# ServoEncoder.net
KiCad netlist of a schematic drawn in EAGLE
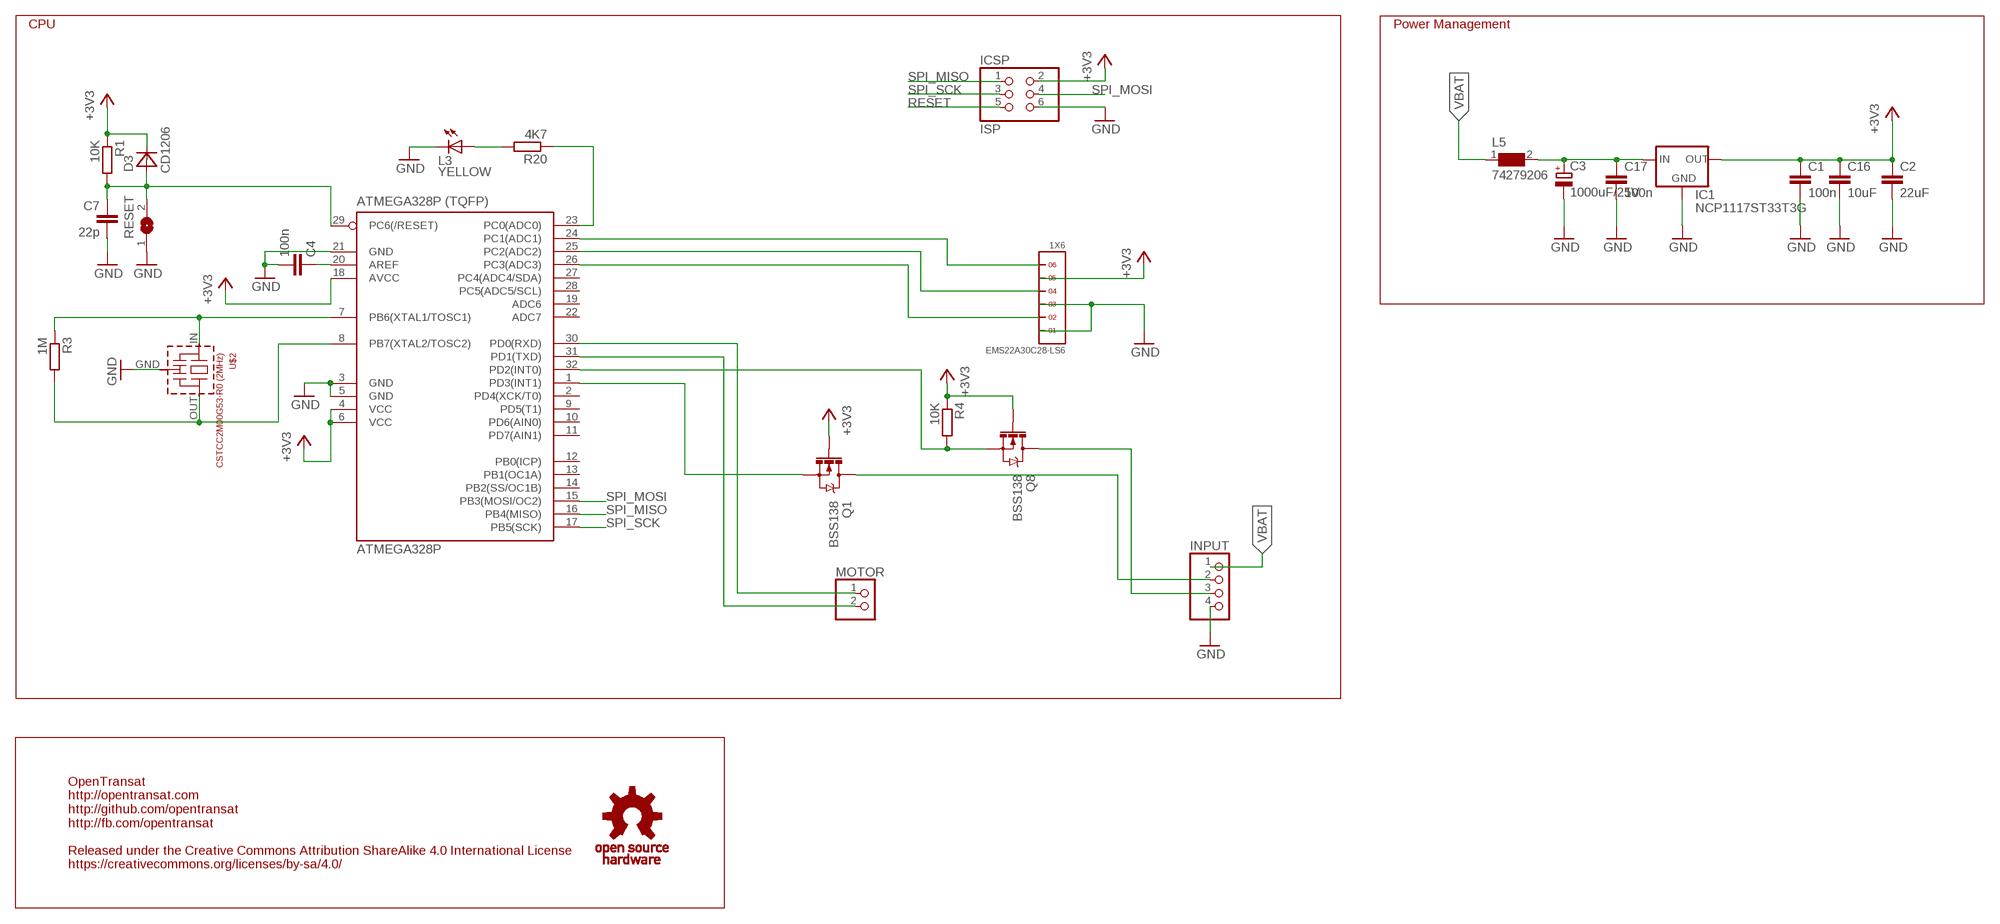
[diagram p0: schematic, sheet 1]

(export (version "E")
  (design (tool "Eeschema 10.0.6"))
  (components
    (comp (ref "ATMEGA328P")
      (value "ATMEGA328P (TQFP)")
      (footprint "eagle-import:TQFP32-08")
      (fields (field (name "MPN") "ATMEGA8-16AU"))
      (libsource (lib "eagle-import") (part "MEGA8-AI"))
    )
    (comp (ref "C1")
      (value "100n")
      (footprint "eagle-import:C0603")
      (libsource (lib "eagle-import") (part "C-EUC0603"))
    )
    (comp (ref "C2")
      (value "22uF")
      (footprint "eagle-import:C1210")
      (libsource (lib "eagle-import") (part "C-EUC1210"))
    )
    (comp (ref "C3")
      (value "1000uF/25V")
      (footprint "eagle-import:E5-10,5")
      (libsource (lib "eagle-import") (part "CPOL-EUE5-10.5"))
    )
    (comp (ref "C4")
      (value "100n")
      (footprint "eagle-import:C0603")
      (libsource (lib "eagle-import") (part "C-EUC0603"))
    )
    (comp (ref "C7")
      (value "22p")
      (footprint "eagle-import:C0603")
      (libsource (lib "eagle-import") (part "C-EUC0603"))
    )
    (comp (ref "C16")
      (value "10uF")
      (footprint "eagle-import:C1206")
      (libsource (lib "eagle-import") (part "C-EUC1206"))
    )
    (comp (ref "C17")
      (value "100n")
      (footprint "eagle-import:C0603")
      (libsource (lib "eagle-import") (part "C-EUC0603"))
    )
    (comp (ref "D3")
      (value "CD1206")
      (footprint "eagle-import:R1206")
      (libsource (lib "eagle-import") (part "CD1206"))
    )
    (comp (ref "EMS22A30C28-LS6")
      (value "1X6")
      (footprint "eagle-import:1X6")
      (libsource (lib "eagle-import") (part "1X6"))
    )
    (comp (ref "IC1")
      (value "NCP1117ST33T3G")
      (footprint "eagle-import:SOT223")
      (fields (field (name "MF") "Texas Instruments") (field (name "MPN") "LM1117MP-3.3"))
      (libsource (lib "eagle-import") (part "LM1117?-MP3.3"))
    )
    (comp (ref "ICSP")
      (value "ISP")
      (footprint "eagle-import:2X03")
      (libsource (lib "eagle-import") (part "PINHD-2X3"))
    )
    (comp (ref "INPUT")
      (value "PINHD-1X4")
      (footprint "eagle-import:1X04")
      (libsource (lib "eagle-import") (part "PINHD-1X4"))
    )
    (comp (ref "L3")
      (value "YELLOW")
      (footprint "eagle-import:CHIPLED_0805")
      (libsource (lib "eagle-import") (part "LEDCHIPLED_0805"))
    )
    (comp (ref "L5")
      (value "74279206")
      (footprint "eagle-import:0805")
      (libsource (lib "eagle-import") (part "WE-CBF_0805"))
    )
    (comp (ref "MOTOR")
      (value "PINHD-1X2")
      (footprint "eagle-import:1X02")
      (libsource (lib "eagle-import") (part "PINHD-1X2"))
    )
    (comp (ref "Q1")
      (value "BSS138")
      (footprint "eagle-import:SOT23-3")
      (libsource (lib "eagle-import") (part "MOSFET-NCHANNEL_SOT23-3"))
    )
    (comp (ref "Q8")
      (value "BSS138")
      (footprint "eagle-import:SOT23-3")
      (libsource (lib "eagle-import") (part "MOSFET-NCHANNEL_SOT23-3"))
    )
    (comp (ref "R1")
      (value "10K")
      (footprint "eagle-import:R0603")
      (libsource (lib "eagle-import") (part "R-EU_R0603"))
    )
    (comp (ref "R3")
      (value "1M")
      (footprint "eagle-import:R0603")
      (libsource (lib "eagle-import") (part "R-EU_R0603"))
    )
    (comp (ref "R4")
      (value "10K")
      (footprint "eagle-import:R0603")
      (libsource (lib "eagle-import") (part "R-EU_R0603"))
    )
    (comp (ref "R20")
      (value "4K7")
      (footprint "eagle-import:R0603")
      (libsource (lib "eagle-import") (part "R-EU_R0603"))
    )
    (comp (ref "RESET")
      (value "SJW")
      (footprint "eagle-import:SJW")
      (libsource (lib "eagle-import") (part "SJW"))
    )
    (comp (ref "U$1")
      (value "OSHW_S")
      (footprint "eagle-import:OSHWS")
      (libsource (lib "eagle-import") (part "OSHW_S"))
    )
    (comp (ref "U$2")
      (value "CSTCC2M00G53-R0 (2MHz)")
      (footprint "eagle-import:CSTCC")
      (libsource (lib "eagle-import") (part "CSTCC"))
    )
  )
  (nets
    (net (code "1") (name "+3V3") (class "Default")
      (node (ref "ATMEGA328P") (pin "18") (pinfunction "AVCC_18") (pintype "power_in"))
      (node (ref "ATMEGA328P") (pin "4") (pinfunction "VCC_4") (pintype "power_in"))
      (node (ref "ATMEGA328P") (pin "6") (pinfunction "VCC_6") (pintype "power_in"))
      (node (ref "C1") (pin "1") (pinfunction "1_1") (pintype "passive"))
      (node (ref "C16") (pin "1") (pinfunction "1_1") (pintype "passive"))
      (node (ref "C2") (pin "1") (pinfunction "1_1") (pintype "passive"))
      (node (ref "D3") (pin "2") (pinfunction "C_2") (pintype "passive"))
      (node (ref "EMS22A30C28-LS6") (pin "5") (pinfunction "5_5") (pintype "bidirectional"))
      (node (ref "IC1") (pin "2") (pinfunction "OUT_2") (pintype "passive"))
      (node (ref "IC1") (pin "4") (pinfunction "OUT_4") (pintype "passive"))
      (node (ref "ICSP") (pin "2") (pinfunction "2_2") (pintype "passive"))
      (node (ref "Q1") (pin "1") (pinfunction "G_1") (pintype "passive"))
      (node (ref "Q8") (pin "1") (pinfunction "G_1") (pintype "passive"))
      (node (ref "R1") (pin "1") (pinfunction "1_1") (pintype "passive"))
      (node (ref "R4") (pin "1") (pinfunction "1_1") (pintype "passive"))
    )
    (net (code "2") (name "/RESET") (class "Default")
      (node (ref "ATMEGA328P") (pin "29") (pinfunction "PC6(/RESET)_29") (pintype "bidirectional"))
      (node (ref "C7") (pin "1") (pinfunction "1_1") (pintype "passive"))
      (node (ref "D3") (pin "1") (pinfunction "A_1") (pintype "passive"))
      (node (ref "ICSP") (pin "5") (pinfunction "5_5") (pintype "passive"))
      (node (ref "R1") (pin "2") (pinfunction "2_2") (pintype "passive"))
      (node (ref "RESET") (pin "2") (pinfunction "2_2") (pintype "passive"))
    )
    (net (code "3") (name "/SPI_MISO") (class "Default")
      (node (ref "ATMEGA328P") (pin "16") (pinfunction "PB4(MISO)_16") (pintype "bidirectional"))
      (node (ref "ICSP") (pin "1") (pinfunction "1_1") (pintype "passive"))
    )
    (net (code "4") (name "/SPI_MOSI") (class "Default")
      (node (ref "ATMEGA328P") (pin "15") (pinfunction "PB3(MOSI/OC2)_15") (pintype "bidirectional"))
      (node (ref "ICSP") (pin "4") (pinfunction "4_4") (pintype "passive"))
    )
    (net (code "5") (name "/SPI_SCK") (class "Default")
      (node (ref "ATMEGA328P") (pin "17") (pinfunction "PB5(SCK)_17") (pintype "bidirectional"))
      (node (ref "ICSP") (pin "3") (pinfunction "3_3") (pintype "passive"))
    )
    (net (code "6") (name "GND") (class "Default")
      (node (ref "ATMEGA328P") (pin "21") (pinfunction "GND_21") (pintype "power_in"))
      (node (ref "ATMEGA328P") (pin "3") (pinfunction "GND_3") (pintype "power_in"))
      (node (ref "ATMEGA328P") (pin "5") (pinfunction "GND_5") (pintype "power_in"))
      (node (ref "C1") (pin "2") (pinfunction "2_2") (pintype "passive"))
      (node (ref "C16") (pin "2") (pinfunction "2_2") (pintype "passive"))
      (node (ref "C17") (pin "2") (pinfunction "2_2") (pintype "passive"))
      (node (ref "C2") (pin "2") (pinfunction "2_2") (pintype "passive"))
      (node (ref "C3") (pin "-") (pinfunction "-_-") (pintype "passive"))
      (node (ref "C4") (pin "2") (pinfunction "2_2") (pintype "passive"))
      (node (ref "C7") (pin "2") (pinfunction "2_2") (pintype "passive"))
      (node (ref "EMS22A30C28-LS6") (pin "1") (pinfunction "1_1") (pintype "bidirectional"))
      (node (ref "EMS22A30C28-LS6") (pin "3") (pinfunction "3_3") (pintype "bidirectional"))
      (node (ref "IC1") (pin "1") (pinfunction "GND_1") (pintype "input"))
      (node (ref "ICSP") (pin "6") (pinfunction "6_6") (pintype "passive"))
      (node (ref "INPUT") (pin "4") (pinfunction "4_4") (pintype "passive"))
      (node (ref "L3") (pin "C") (pinfunction "C_C") (pintype "passive"))
      (node (ref "RESET") (pin "1") (pinfunction "1_1") (pintype "passive"))
      (node (ref "U$2") (pin "GND") (pinfunction "GND_GND") (pintype "power_in"))
    )
    (net (code "7") (name "Net-(ATMEGA328P-AREF)") (class "Default")
      (node (ref "ATMEGA328P") (pin "20") (pinfunction "AREF_20") (pintype "passive"))
      (node (ref "C4") (pin "1") (pinfunction "1_1") (pintype "passive"))
    )
    (net (code "8") (name "Net-(ATMEGA328P-PB6(XTAL1{slash}TOSC1))") (class "Default")
      (node (ref "ATMEGA328P") (pin "7") (pinfunction "PB6(XTAL1/TOSC1)_7") (pintype "bidirectional"))
      (node (ref "R3") (pin "1") (pinfunction "1_1") (pintype "passive"))
      (node (ref "U$2") (pin "IN") (pinfunction "IN_IN") (pintype "input"))
    )
    (net (code "9") (name "Net-(ATMEGA328P-PB7(XTAL2{slash}TOSC2))") (class "Default")
      (node (ref "ATMEGA328P") (pin "8") (pinfunction "PB7(XTAL2/TOSC2)_8") (pintype "bidirectional"))
      (node (ref "R3") (pin "2") (pinfunction "2_2") (pintype "passive"))
      (node (ref "U$2") (pin "OUT") (pinfunction "OUT_OUT") (pintype "output"))
    )
    (net (code "10") (name "Net-(ATMEGA328P-PC0(ADC0))") (class "Default")
      (node (ref "ATMEGA328P") (pin "23") (pinfunction "PC0(ADC0)_23") (pintype "bidirectional"))
      (node (ref "R20") (pin "1") (pinfunction "1_1") (pintype "passive"))
    )
    (net (code "11") (name "Net-(ATMEGA328P-PC1(ADC1))") (class "Default")
      (node (ref "ATMEGA328P") (pin "24") (pinfunction "PC1(ADC1)_24") (pintype "bidirectional"))
      (node (ref "EMS22A30C28-LS6") (pin "6") (pinfunction "6_6") (pintype "bidirectional"))
    )
    (net (code "12") (name "Net-(ATMEGA328P-PC2(ADC2))") (class "Default")
      (node (ref "ATMEGA328P") (pin "25") (pinfunction "PC2(ADC2)_25") (pintype "bidirectional"))
      (node (ref "EMS22A30C28-LS6") (pin "4") (pinfunction "4_4") (pintype "bidirectional"))
    )
    (net (code "13") (name "Net-(ATMEGA328P-PC3(ADC3))") (class "Default")
      (node (ref "ATMEGA328P") (pin "26") (pinfunction "PC3(ADC3)_26") (pintype "bidirectional"))
      (node (ref "EMS22A30C28-LS6") (pin "2") (pinfunction "2_2") (pintype "bidirectional"))
    )
    (net (code "14") (name "Net-(ATMEGA328P-PD0(RXD))") (class "Default")
      (node (ref "ATMEGA328P") (pin "30") (pinfunction "PD0(RXD)_30") (pintype "bidirectional"))
      (node (ref "MOTOR") (pin "1") (pinfunction "1_1") (pintype "passive"))
    )
    (net (code "15") (name "Net-(ATMEGA328P-PD1(TXD))") (class "Default")
      (node (ref "ATMEGA328P") (pin "31") (pinfunction "PD1(TXD)_31") (pintype "bidirectional"))
      (node (ref "MOTOR") (pin "2") (pinfunction "2_2") (pintype "passive"))
    )
    (net (code "16") (name "Net-(ATMEGA328P-PD2(INT0))") (class "Default")
      (node (ref "ATMEGA328P") (pin "32") (pinfunction "PD2(INT0)_32") (pintype "bidirectional"))
      (node (ref "Q8") (pin "2") (pinfunction "S_2") (pintype "passive"))
      (node (ref "R4") (pin "2") (pinfunction "2_2") (pintype "passive"))
    )
    (net (code "17") (name "Net-(ATMEGA328P-PD3(INT1))") (class "Default")
      (node (ref "ATMEGA328P") (pin "1") (pinfunction "PD3(INT1)_1") (pintype "bidirectional"))
      (node (ref "Q1") (pin "2") (pinfunction "S_2") (pintype "passive"))
    )
    (net (code "18") (name "Net-(IC1-IN)") (class "Default")
      (node (ref "C17") (pin "1") (pinfunction "1_1") (pintype "passive"))
      (node (ref "C3") (pin "+") (pinfunction "+_+") (pintype "passive"))
      (node (ref "IC1") (pin "3") (pinfunction "IN_3") (pintype "input"))
      (node (ref "L5") (pin "2") (pinfunction "2_2") (pintype "passive"))
    )
    (net (code "19") (name "Net-(L3-PadA)") (class "Default")
      (node (ref "L3") (pin "A") (pinfunction "A_A") (pintype "passive"))
      (node (ref "R20") (pin "2") (pinfunction "2_2") (pintype "passive"))
    )
    (net (code "20") (name "Net-(Q1-D)") (class "Default")
      (node (ref "INPUT") (pin "2") (pinfunction "2_2") (pintype "passive"))
      (node (ref "Q1") (pin "3") (pinfunction "D_3") (pintype "passive"))
    )
    (net (code "21") (name "Net-(Q8-D)") (class "Default")
      (node (ref "INPUT") (pin "3") (pinfunction "3_3") (pintype "passive"))
      (node (ref "Q8") (pin "3") (pinfunction "D_3") (pintype "passive"))
    )
    (net (code "22") (name "VBAT") (class "Default")
      (node (ref "INPUT") (pin "1") (pinfunction "1_1") (pintype "passive"))
      (node (ref "L5") (pin "1") (pinfunction "1_1") (pintype "passive"))
    )
    (net (code "23") (name "unconnected-(ATMEGA328P-ADC6-Pad19)") (class "Default")
      (node (ref "ATMEGA328P") (pin "19") (pinfunction "ADC6_19") (pintype "bidirectional"))
    )
    (net (code "24") (name "unconnected-(ATMEGA328P-ADC7-Pad22)") (class "Default")
      (node (ref "ATMEGA328P") (pin "22") (pinfunction "ADC7_22") (pintype "bidirectional"))
    )
    (net (code "25") (name "unconnected-(ATMEGA328P-PB0(ICP)-Pad12)") (class "Default")
      (node (ref "ATMEGA328P") (pin "12") (pinfunction "PB0(ICP)_12") (pintype "bidirectional"))
    )
    (net (code "26") (name "unconnected-(ATMEGA328P-PB1(OC1A)-Pad13)") (class "Default")
      (node (ref "ATMEGA328P") (pin "13") (pinfunction "PB1(OC1A)_13") (pintype "bidirectional"))
    )
    (net (code "27") (name "unconnected-(ATMEGA328P-PB2(SS{slash}OC1B)-Pad14)") (class "Default")
      (node (ref "ATMEGA328P") (pin "14") (pinfunction "PB2(SS/OC1B)_14") (pintype "bidirectional"))
    )
    (net (code "28") (name "unconnected-(ATMEGA328P-PC4(ADC4{slash}SDA)-Pad27)") (class "Default")
      (node (ref "ATMEGA328P") (pin "27") (pinfunction "PC4(ADC4/SDA)_27") (pintype "bidirectional"))
    )
    (net (code "29") (name "unconnected-(ATMEGA328P-PC5(ADC5{slash}SCL)-Pad28)") (class "Default")
      (node (ref "ATMEGA328P") (pin "28") (pinfunction "PC5(ADC5/SCL)_28") (pintype "bidirectional"))
    )
    (net (code "30") (name "unconnected-(ATMEGA328P-PD4(XCK{slash}T0)-Pad2)") (class "Default")
      (node (ref "ATMEGA328P") (pin "2") (pinfunction "PD4(XCK/T0)_2") (pintype "bidirectional"))
    )
    (net (code "31") (name "unconnected-(ATMEGA328P-PD5(T1)-Pad9)") (class "Default")
      (node (ref "ATMEGA328P") (pin "9") (pinfunction "PD5(T1)_9") (pintype "bidirectional"))
    )
    (net (code "32") (name "unconnected-(ATMEGA328P-PD6(AIN0)-Pad10)") (class "Default")
      (node (ref "ATMEGA328P") (pin "10") (pinfunction "PD6(AIN0)_10") (pintype "bidirectional"))
    )
    (net (code "33") (name "unconnected-(ATMEGA328P-PD7(AIN1)-Pad11)") (class "Default")
      (node (ref "ATMEGA328P") (pin "11") (pinfunction "PD7(AIN1)_11") (pintype "bidirectional"))
    )
  )
)
